# Moteino.net
KiCad netlist of a schematic drawn in EAGLE
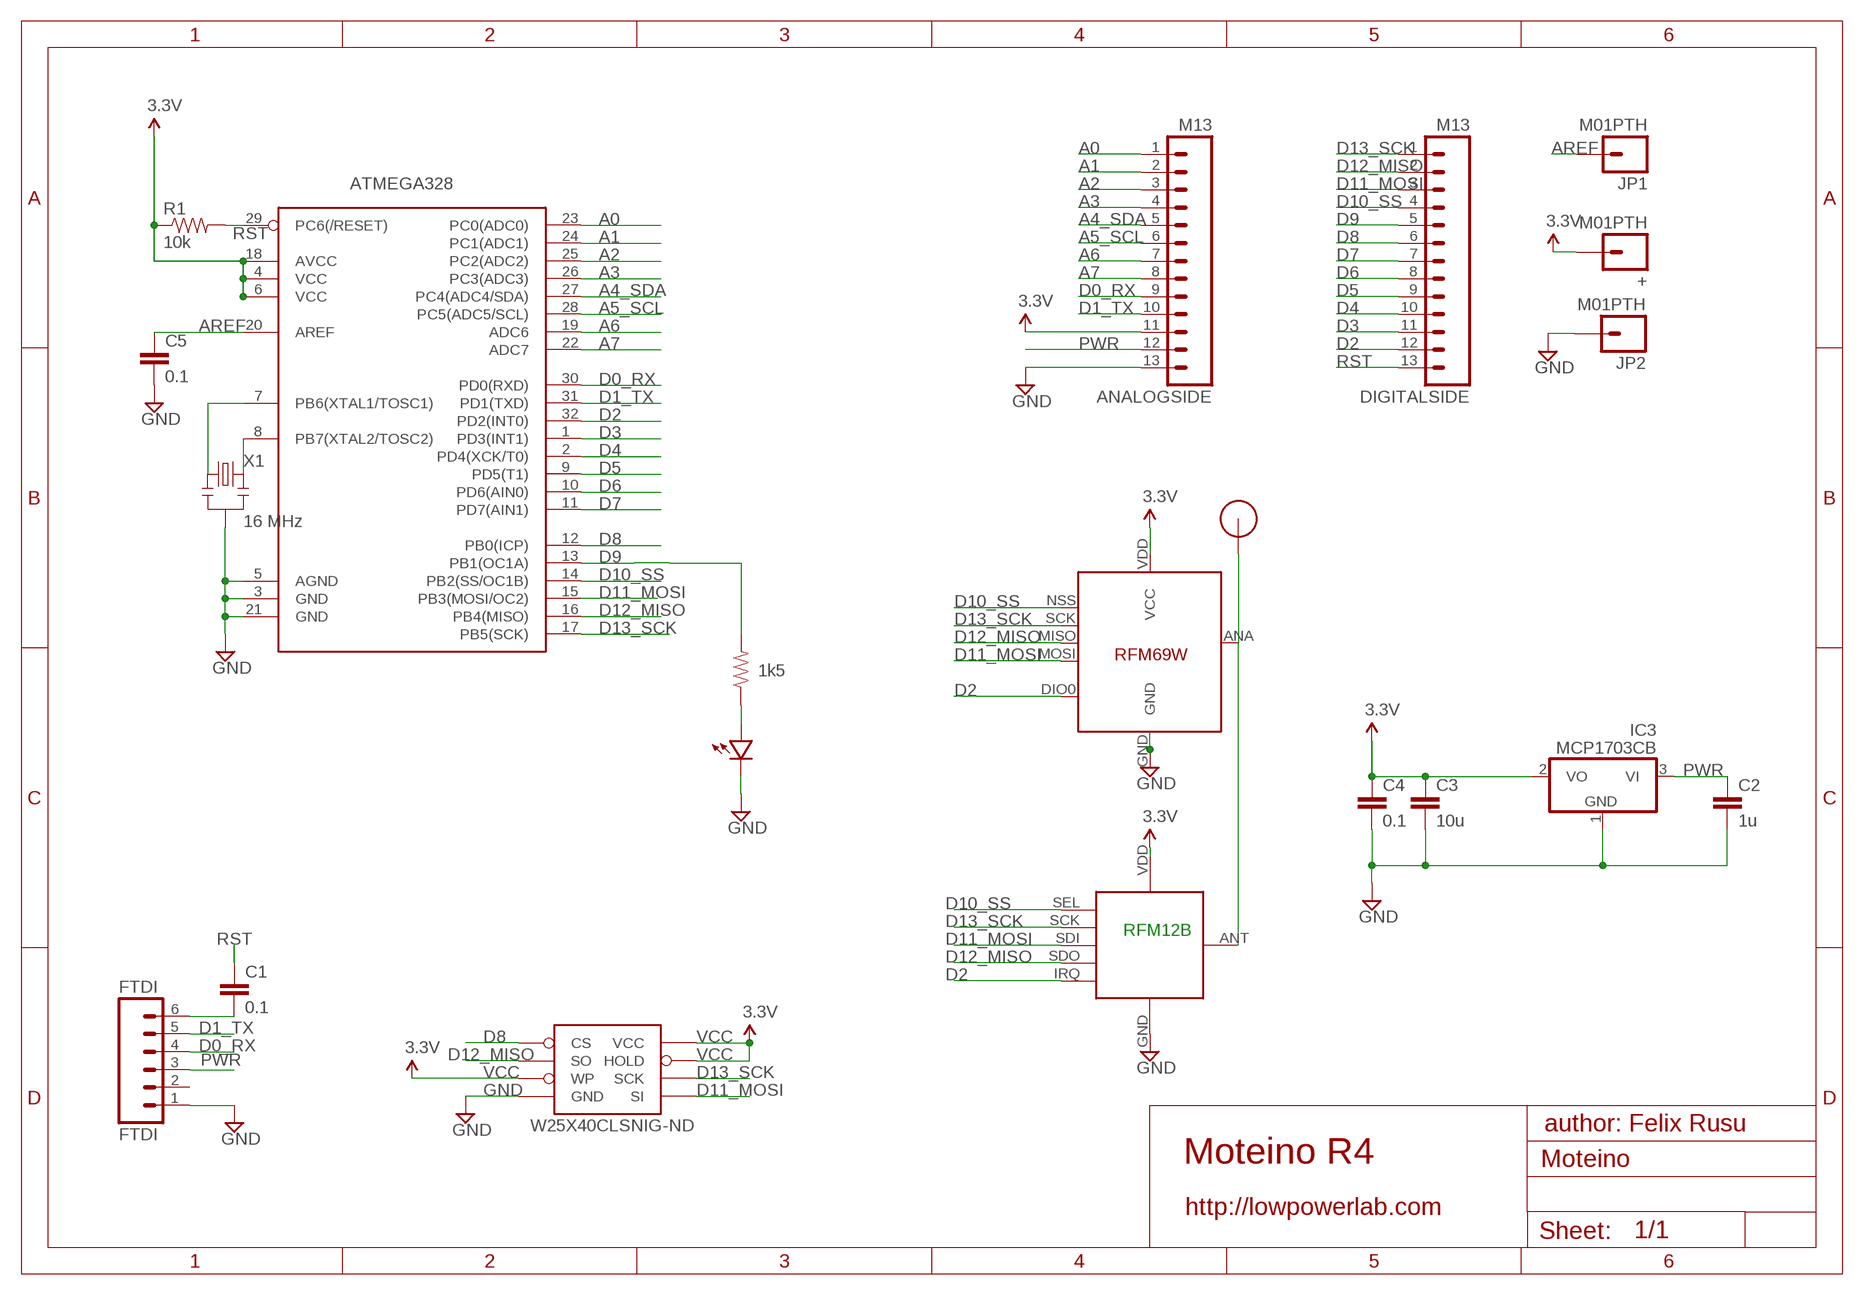
[diagram p0: schematic, sheet 1]

(export (version "E")
  (design (tool "Eeschema 10.0.6"))
  (components
    (comp (ref "+")
      (value "M01PTH")
      (footprint "eagle-import:1X01")
      (libsource (lib "eagle-import") (part "M01PTH"))
    )
    (comp (ref "ANALOGSIDE")
      (value "M13")
      (footprint "eagle-import:1X13")
      (libsource (lib "eagle-import") (part "M13"))
    )
    (comp (ref "ATMEGA328")
      (value "ATMega-328")
      (footprint "eagle-import:TQFP32-08")
      (libsource (lib "eagle-import") (part "ATMEGA168/328TQFP32"))
    )
    (comp (ref "C1")
      (value "0.1")
      (footprint "eagle-import:0603-CAP")
      (libsource (lib "eagle-import") (part "CAP0603-CAP"))
    )
    (comp (ref "C2")
      (value "1u")
      (footprint "eagle-import:0603-CAP")
      (libsource (lib "eagle-import") (part "CAP0603-CAP"))
    )
    (comp (ref "C3")
      (value "10u")
      (footprint "eagle-import:0805-CAP")
      (libsource (lib "eagle-import") (part "CAP0805-CAP"))
    )
    (comp (ref "C4")
      (value "0.1")
      (footprint "eagle-import:0603-CAP")
      (libsource (lib "eagle-import") (part "CAP0603-CAP"))
    )
    (comp (ref "C5")
      (value "0.1")
      (footprint "eagle-import:0603-CAP")
      (libsource (lib "eagle-import") (part "CAP0603-CAP"))
    )
    (comp (ref "DIGITALSIDE")
      (value "M13")
      (footprint "eagle-import:1X13")
      (libsource (lib "eagle-import") (part "M13"))
    )
    (comp (ref "FTDI")
      (value "FTDI")
      (footprint "eagle-import:1X06")
      (libsource (lib "eagle-import") (part "M06SIP"))
    )
    (comp (ref "IC3")
      (value "MCP1703CB")
      (footprint "eagle-import:SOT23")
      (libsource (lib "eagle-import") (part "MCP1703CB"))
    )
    (comp (ref "JP1")
      (value "M01PTH")
      (footprint "eagle-import:1X01")
      (libsource (lib "eagle-import") (part "M01PTH"))
    )
    (comp (ref "JP2")
      (value "M01PTH")
      (footprint "eagle-import:1X01")
      (libsource (lib "eagle-import") (part "M01PTH"))
    )
    (comp (ref "R1")
      (value "10k")
      (footprint "eagle-import:0603-RES")
      (libsource (lib "eagle-import") (part "RESISTOR0603-RES"))
    )
    (comp (ref "R2")
      (value "1k5")
      (footprint "eagle-import:0603-RES")
      (libsource (lib "eagle-import") (part "RESISTOR0603-RES"))
    )
    (comp (ref "RFM12B")
      (value "RFM12B_MINPADS")
      (footprint "eagle-import:RFM12B-MINPADS")
      (libsource (lib "eagle-import") (part "RFM12B_MINPADS"))
    )
    (comp (ref "U$1")
      (value "RFM12B_ANTENNA")
      (footprint "eagle-import:RFM12B-ANTENNA")
      (libsource (lib "eagle-import") (part "RFM12B_ANTENNA"))
    )
    (comp (ref "U$2")
      (value "LED0603")
      (footprint "eagle-import:0603-LED")
      (libsource (lib "eagle-import") (part "LED0603"))
    )
    (comp (ref "U$5")
      (value "RFM69")
      (footprint "eagle-import:RFM69W-MINPADS")
      (libsource (lib "eagle-import") (part "RFM69"))
    )
    (comp (ref "W25X40CLSNIG-ND")
      (value "AT25F512BWIDE_5.3MM")
      (footprint "eagle-import:SO08WIDE")
      (libsource (lib "eagle-import") (part "AT25F512BWIDE_5.3MM"))
    )
    (comp (ref "X1")
      (value "16 MHz")
      (footprint "eagle-import:RESONATOR-SMD")
      (libsource (lib "eagle-import") (part "RESONATORSMD"))
    )
  )
  (nets
    (net (code "1") (name "/A0") (class "Default")
      (node (ref "ANALOGSIDE") (pin "1") (pinfunction "1_1") (pintype "passive"))
      (node (ref "ATMEGA328") (pin "23") (pinfunction "PC0(ADC0)_23") (pintype "bidirectional"))
    )
    (net (code "2") (name "/A1") (class "Default")
      (node (ref "ANALOGSIDE") (pin "2") (pinfunction "2_2") (pintype "passive"))
      (node (ref "ATMEGA328") (pin "24") (pinfunction "PC1(ADC1)_24") (pintype "bidirectional"))
    )
    (net (code "3") (name "/A2") (class "Default")
      (node (ref "ANALOGSIDE") (pin "3") (pinfunction "3_3") (pintype "passive"))
      (node (ref "ATMEGA328") (pin "25") (pinfunction "PC2(ADC2)_25") (pintype "bidirectional"))
    )
    (net (code "4") (name "/A3") (class "Default")
      (node (ref "ANALOGSIDE") (pin "4") (pinfunction "4_4") (pintype "passive"))
      (node (ref "ATMEGA328") (pin "26") (pinfunction "PC3(ADC3)_26") (pintype "bidirectional"))
    )
    (net (code "5") (name "/A4_SDA") (class "Default")
      (node (ref "ANALOGSIDE") (pin "5") (pinfunction "5_5") (pintype "passive"))
      (node (ref "ATMEGA328") (pin "27") (pinfunction "PC4(ADC4/SDA)_27") (pintype "bidirectional"))
    )
    (net (code "6") (name "/A5_SCL") (class "Default")
      (node (ref "ANALOGSIDE") (pin "6") (pinfunction "6_6") (pintype "passive"))
      (node (ref "ATMEGA328") (pin "28") (pinfunction "PC5(ADC5/SCL)_28") (pintype "bidirectional"))
    )
    (net (code "7") (name "/A6") (class "Default")
      (node (ref "ANALOGSIDE") (pin "7") (pinfunction "7_7") (pintype "passive"))
      (node (ref "ATMEGA328") (pin "19") (pinfunction "ADC6_19") (pintype "bidirectional"))
    )
    (net (code "8") (name "/A7") (class "Default")
      (node (ref "ANALOGSIDE") (pin "8") (pinfunction "8_8") (pintype "passive"))
      (node (ref "ATMEGA328") (pin "22") (pinfunction "ADC7_22") (pintype "bidirectional"))
    )
    (net (code "9") (name "/AREF") (class "Default")
      (node (ref "ATMEGA328") (pin "20") (pinfunction "AREF_20") (pintype "bidirectional"))
      (node (ref "C5") (pin "1") (pinfunction "1_1") (pintype "passive"))
      (node (ref "JP1") (pin "1") (pinfunction "1_1") (pintype "passive"))
    )
    (net (code "10") (name "/D0_RX") (class "Default")
      (node (ref "ANALOGSIDE") (pin "9") (pinfunction "9_9") (pintype "passive"))
      (node (ref "ATMEGA328") (pin "30") (pinfunction "PD0(RXD)_30") (pintype "bidirectional"))
      (node (ref "FTDI") (pin "4") (pinfunction "4_4") (pintype "passive"))
    )
    (net (code "11") (name "/D1_TX") (class "Default")
      (node (ref "ANALOGSIDE") (pin "10") (pinfunction "10_10") (pintype "passive"))
      (node (ref "ATMEGA328") (pin "31") (pinfunction "PD1(TXD)_31") (pintype "bidirectional"))
      (node (ref "FTDI") (pin "5") (pinfunction "5_5") (pintype "passive"))
    )
    (net (code "12") (name "/D2") (class "Default")
      (node (ref "ATMEGA328") (pin "32") (pinfunction "PD2(INT0)_32") (pintype "bidirectional"))
      (node (ref "DIGITALSIDE") (pin "12") (pinfunction "12_12") (pintype "passive"))
      (node (ref "RFM12B") (pin "IRQ") (pinfunction "IRQ_IRQ") (pintype "bidirectional"))
      (node (ref "U$5") (pin "DIO0") (pinfunction "DIO0_DIO0") (pintype "open_collector"))
    )
    (net (code "13") (name "/D3") (class "Default")
      (node (ref "ATMEGA328") (pin "1") (pinfunction "PD3(INT1)_1") (pintype "bidirectional"))
      (node (ref "DIGITALSIDE") (pin "11") (pinfunction "11_11") (pintype "passive"))
    )
    (net (code "14") (name "/D4") (class "Default")
      (node (ref "ATMEGA328") (pin "2") (pinfunction "PD4(XCK/T0)_2") (pintype "bidirectional"))
      (node (ref "DIGITALSIDE") (pin "10") (pinfunction "10_10") (pintype "passive"))
    )
    (net (code "15") (name "/D5") (class "Default")
      (node (ref "ATMEGA328") (pin "9") (pinfunction "PD5(T1)_9") (pintype "bidirectional"))
      (node (ref "DIGITALSIDE") (pin "9") (pinfunction "9_9") (pintype "passive"))
    )
    (net (code "16") (name "/D6") (class "Default")
      (node (ref "ATMEGA328") (pin "10") (pinfunction "PD6(AIN0)_10") (pintype "bidirectional"))
      (node (ref "DIGITALSIDE") (pin "8") (pinfunction "8_8") (pintype "passive"))
    )
    (net (code "17") (name "/D7") (class "Default")
      (node (ref "ATMEGA328") (pin "11") (pinfunction "PD7(AIN1)_11") (pintype "bidirectional"))
      (node (ref "DIGITALSIDE") (pin "7") (pinfunction "7_7") (pintype "passive"))
    )
    (net (code "18") (name "/D8") (class "Default")
      (node (ref "ATMEGA328") (pin "12") (pinfunction "PB0(ICP)_12") (pintype "bidirectional"))
      (node (ref "DIGITALSIDE") (pin "6") (pinfunction "6_6") (pintype "passive"))
      (node (ref "W25X40CLSNIG-ND") (pin "1") (pinfunction "CS_1") (pintype "bidirectional"))
    )
    (net (code "19") (name "/D9") (class "Default")
      (node (ref "ATMEGA328") (pin "13") (pinfunction "PB1(OC1A)_13") (pintype "bidirectional"))
      (node (ref "DIGITALSIDE") (pin "5") (pinfunction "5_5") (pintype "passive"))
      (node (ref "R2") (pin "2") (pinfunction "2_2") (pintype "passive"))
    )
    (net (code "20") (name "/D10_SS") (class "Default")
      (node (ref "ATMEGA328") (pin "14") (pinfunction "PB2(SS/OC1B)_14") (pintype "bidirectional"))
      (node (ref "DIGITALSIDE") (pin "4") (pinfunction "4_4") (pintype "passive"))
      (node (ref "RFM12B") (pin "SEL") (pinfunction "SEL_SEL") (pintype "bidirectional"))
      (node (ref "U$5") (pin "NSS") (pinfunction "SEL_NSS") (pintype "input"))
    )
    (net (code "21") (name "/D11_MOSI") (class "Default")
      (node (ref "ATMEGA328") (pin "15") (pinfunction "PB3(MOSI/OC2)_15") (pintype "bidirectional"))
      (node (ref "DIGITALSIDE") (pin "3") (pinfunction "3_3") (pintype "passive"))
      (node (ref "RFM12B") (pin "SDI") (pinfunction "SDI/MOSI_SDI") (pintype "bidirectional"))
      (node (ref "U$5") (pin "MOSI") (pinfunction "MOSI_MOSI") (pintype "output"))
      (node (ref "W25X40CLSNIG-ND") (pin "5") (pinfunction "SI_5") (pintype "bidirectional"))
    )
    (net (code "22") (name "/D12_MISO") (class "Default")
      (node (ref "ATMEGA328") (pin "16") (pinfunction "PB4(MISO)_16") (pintype "bidirectional"))
      (node (ref "DIGITALSIDE") (pin "2") (pinfunction "2_2") (pintype "passive"))
      (node (ref "RFM12B") (pin "SDO") (pinfunction "SDO/MISO_SDO") (pintype "bidirectional"))
      (node (ref "U$5") (pin "MISO") (pinfunction "MISO_MISO") (pintype "input"))
      (node (ref "W25X40CLSNIG-ND") (pin "2") (pinfunction "SO_2") (pintype "bidirectional"))
    )
    (net (code "23") (name "/D13_SCK") (class "Default")
      (node (ref "ATMEGA328") (pin "17") (pinfunction "PB5(SCK)_17") (pintype "bidirectional"))
      (node (ref "DIGITALSIDE") (pin "1") (pinfunction "1_1") (pintype "passive"))
      (node (ref "RFM12B") (pin "SCK") (pinfunction "SCK_SCK") (pintype "bidirectional"))
      (node (ref "U$5") (pin "SCK") (pinfunction "SCK_SCK") (pintype "input"))
      (node (ref "W25X40CLSNIG-ND") (pin "6") (pinfunction "SCK_6") (pintype "bidirectional"))
    )
    (net (code "24") (name "/PWR") (class "Default")
      (node (ref "ANALOGSIDE") (pin "12") (pinfunction "12_12") (pintype "passive"))
      (node (ref "C2") (pin "1") (pinfunction "1_1") (pintype "passive"))
      (node (ref "FTDI") (pin "3") (pinfunction "3_3") (pintype "passive"))
      (node (ref "IC3") (pin "3") (pinfunction "VI_3") (pintype "input"))
    )
    (net (code "25") (name "/RST") (class "Default")
      (node (ref "ATMEGA328") (pin "29") (pinfunction "PC6(/RESET)_29") (pintype "bidirectional"))
      (node (ref "C1") (pin "1") (pinfunction "1_1") (pintype "passive"))
      (node (ref "DIGITALSIDE") (pin "13") (pinfunction "13_13") (pintype "passive"))
      (node (ref "R1") (pin "2") (pinfunction "2_2") (pintype "passive"))
    )
    (net (code "26") (name "3.3V") (class "Default")
      (node (ref "+") (pin "1") (pinfunction "1_1") (pintype "passive"))
      (node (ref "ANALOGSIDE") (pin "11") (pinfunction "11_11") (pintype "passive"))
      (node (ref "ATMEGA328") (pin "18") (pinfunction "AVCC_18") (pintype "bidirectional"))
      (node (ref "ATMEGA328") (pin "4") (pinfunction "VCC_4") (pintype "bidirectional"))
      (node (ref "ATMEGA328") (pin "6") (pinfunction "VCC_6") (pintype "bidirectional"))
      (node (ref "C3") (pin "1") (pinfunction "1_1") (pintype "passive"))
      (node (ref "C4") (pin "1") (pinfunction "1_1") (pintype "passive"))
      (node (ref "IC3") (pin "2") (pinfunction "VO_2") (pintype "passive"))
      (node (ref "R1") (pin "1") (pinfunction "1_1") (pintype "passive"))
      (node (ref "RFM12B") (pin "VDD") (pinfunction "VDD_VDD") (pintype "bidirectional"))
      (node (ref "U$5") (pin "VDD") (pinfunction "VCC_VDD") (pintype "power_in"))
      (node (ref "W25X40CLSNIG-ND") (pin "3") (pinfunction "WP_3") (pintype "bidirectional"))
      (node (ref "W25X40CLSNIG-ND") (pin "7") (pinfunction "HOLD_7") (pintype "bidirectional"))
      (node (ref "W25X40CLSNIG-ND") (pin "8") (pinfunction "VCC_8") (pintype "bidirectional"))
    )
    (net (code "27") (name "GND") (class "Default")
      (node (ref "ANALOGSIDE") (pin "13") (pinfunction "13_13") (pintype "passive"))
      (node (ref "ATMEGA328") (pin "21") (pinfunction "GND_21") (pintype "bidirectional"))
      (node (ref "ATMEGA328") (pin "3") (pinfunction "GND_3") (pintype "bidirectional"))
      (node (ref "ATMEGA328") (pin "5") (pinfunction "AGND_5") (pintype "bidirectional"))
      (node (ref "C2") (pin "2") (pinfunction "2_2") (pintype "passive"))
      (node (ref "C3") (pin "2") (pinfunction "2_2") (pintype "passive"))
      (node (ref "C4") (pin "2") (pinfunction "2_2") (pintype "passive"))
      (node (ref "C5") (pin "2") (pinfunction "2_2") (pintype "passive"))
      (node (ref "FTDI") (pin "1") (pinfunction "1_1") (pintype "passive"))
      (node (ref "IC3") (pin "1") (pinfunction "GND_1") (pintype "passive"))
      (node (ref "JP2") (pin "1") (pinfunction "1_1") (pintype "passive"))
      (node (ref "RFM12B") (pin "GND") (pinfunction "GND_GND") (pintype "bidirectional"))
      (node (ref "U$2") (pin "MINUS") (pinfunction "MINUS_MINUS") (pintype "passive"))
      (node (ref "U$5") (pin "GND") (pinfunction "GND_GND") (pintype "power_in"))
      (node (ref "W25X40CLSNIG-ND") (pin "4") (pinfunction "GND_4") (pintype "bidirectional"))
      (node (ref "X1") (pin "2") (pinfunction "2_2") (pintype "passive"))
    )
    (net (code "28") (name "Net-(ATMEGA328-PB6(XTAL1{slash}TOSC1))") (class "Default")
      (node (ref "ATMEGA328") (pin "7") (pinfunction "PB6(XTAL1/TOSC1)_7") (pintype "bidirectional"))
      (node (ref "X1") (pin "1") (pinfunction "1_1") (pintype "passive"))
    )
    (net (code "29") (name "Net-(ATMEGA328-PB7(XTAL2{slash}TOSC2))") (class "Default")
      (node (ref "ATMEGA328") (pin "8") (pinfunction "PB7(XTAL2/TOSC2)_8") (pintype "bidirectional"))
      (node (ref "X1") (pin "3") (pinfunction "3_3") (pintype "passive"))
    )
    (net (code "30") (name "Net-(C1-Pad2)") (class "Default")
      (node (ref "C1") (pin "2") (pinfunction "2_2") (pintype "passive"))
      (node (ref "FTDI") (pin "6") (pinfunction "6_6") (pintype "passive"))
    )
    (net (code "31") (name "Net-(R2-Pad1)") (class "Default")
      (node (ref "R2") (pin "1") (pinfunction "1_1") (pintype "passive"))
      (node (ref "U$2") (pin "PLUS") (pinfunction "PLUS_PLUS") (pintype "passive"))
    )
    (net (code "32") (name "Net-(U$1-1)") (class "Default")
      (node (ref "RFM12B") (pin "ANT") (pinfunction "ANT_ANT") (pintype "bidirectional"))
      (node (ref "U$1") (pin "P$1") (pinfunction "1_P$1") (pintype "bidirectional"))
      (node (ref "U$5") (pin "ANA") (pinfunction "ANT_ANA") (pintype "passive"))
    )
    (net (code "33") (name "unconnected-(FTDI-Pad2)") (class "Default")
      (node (ref "FTDI") (pin "2") (pinfunction "2_2") (pintype "passive"))
    )
  )
)
